# MCU.net
KiCad netlist of a schematic drawn in Altium Designer
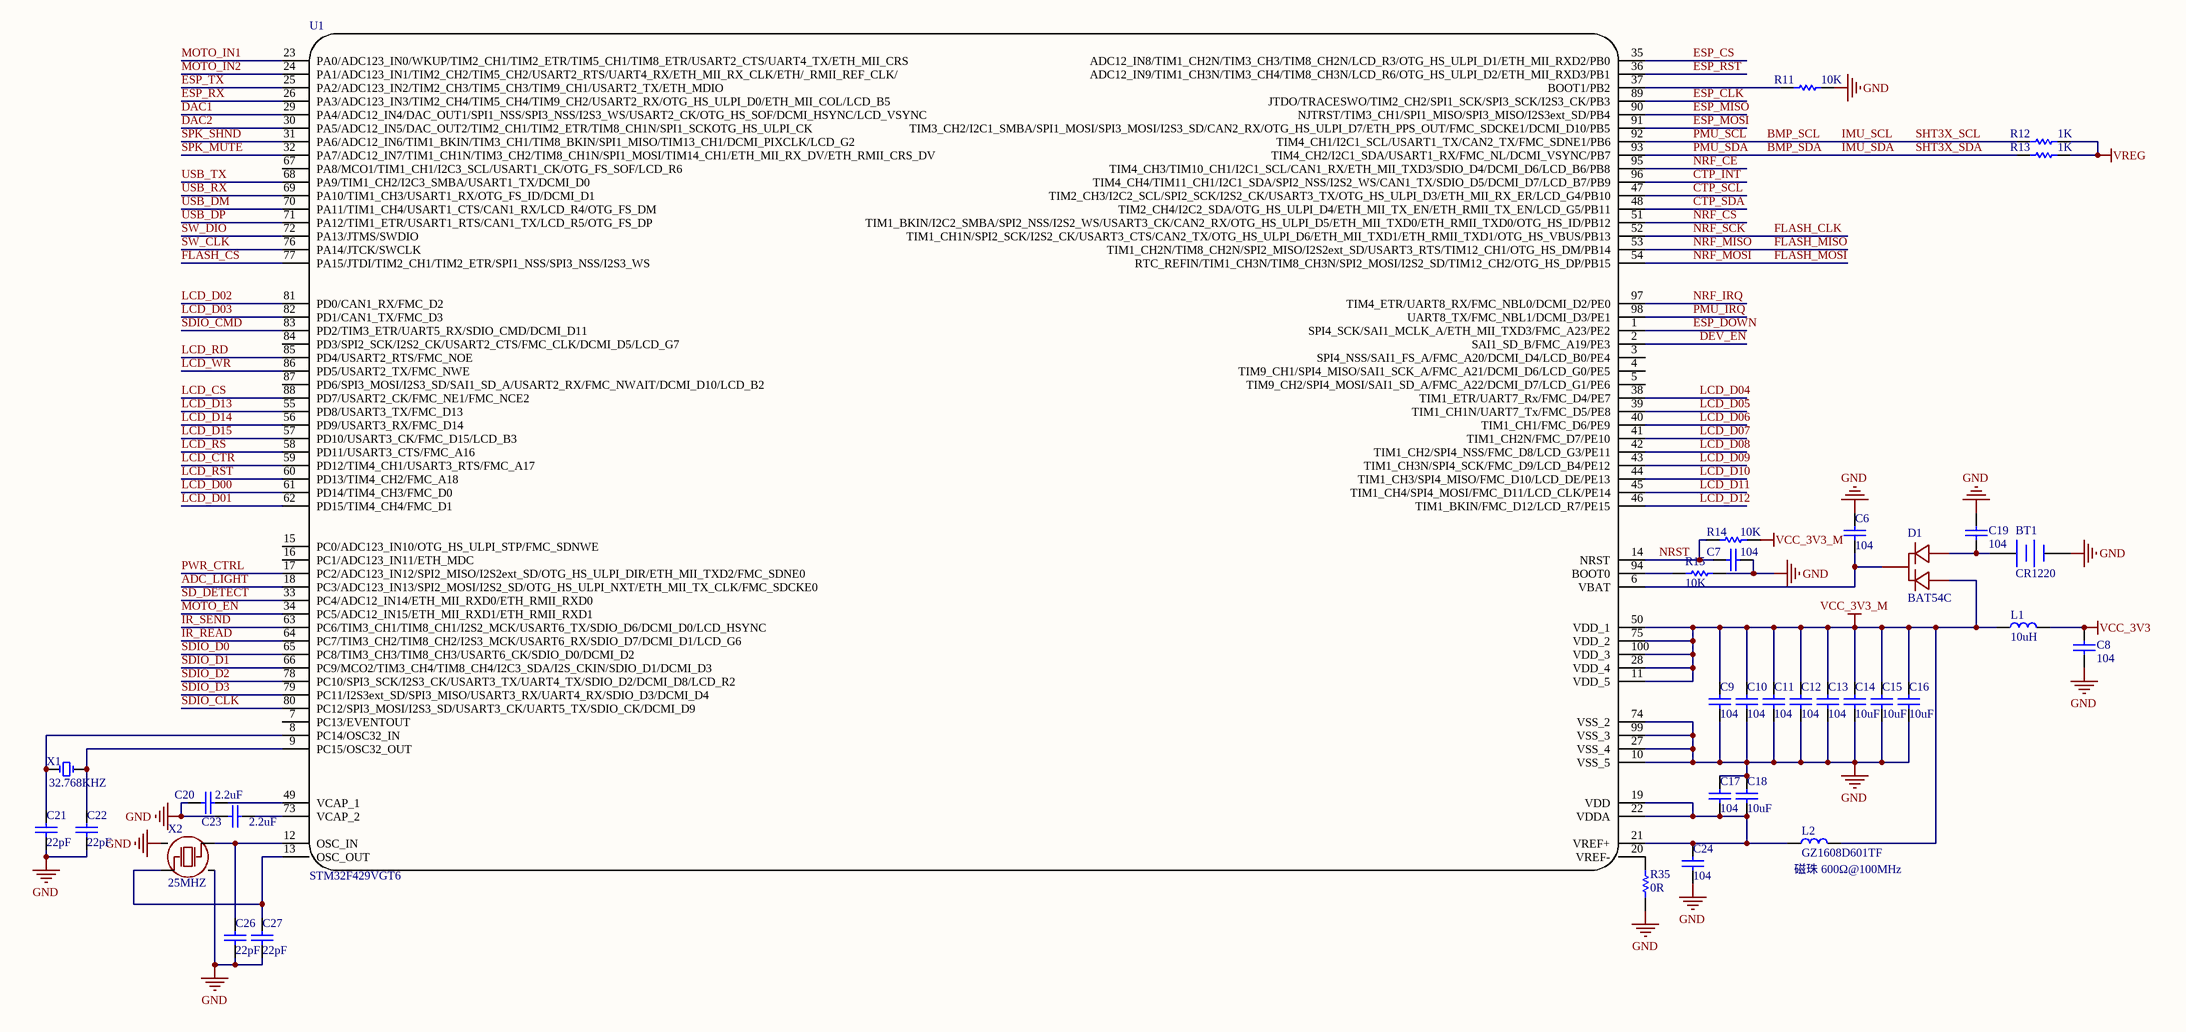
[diagram p0: MCU.SchDoc]

(export (version "E")
  (design (tool "Eeschema 10.0.6"))
  (components
    (comp (ref "BT1")
      (value "CR1220")
      (footprint "CR1220-2")
      (description "Multicell Battery")
      (fields (field (name "PUBLISHER") "Altium Limited"))
      (libsource (lib "Miscellaneous Devices") (part "Battery"))
    )
    (comp (ref "C6") (value "104") (footprint "C 0603") (libsource (lib "Sheet") (part "CAP")))
    (comp (ref "C7") (value "104") (footprint "C 0603") (libsource (lib "Sheet") (part "CAP")))
    (comp (ref "C8") (value "104") (footprint "C 0603") (libsource (lib "Sheet") (part "CAP")))
    (comp (ref "C9") (value "104") (footprint "C 0603") (libsource (lib "Sheet") (part "CAP")))
    (comp (ref "C10") (value "104") (footprint "C 0603") (libsource (lib "Sheet") (part "CAP")))
    (comp (ref "C11") (value "104") (footprint "C 0603") (libsource (lib "Sheet") (part "CAP")))
    (comp (ref "C12") (value "104") (footprint "C 0603") (libsource (lib "Sheet") (part "CAP")))
    (comp (ref "C13") (value "104") (footprint "C 0603") (libsource (lib "Sheet") (part "CAP")))
    (comp (ref "C14") (value "10uF") (footprint "C 0603") (libsource (lib "Sheet") (part "CAP")))
    (comp (ref "C15") (value "10uF") (footprint "C 0603") (libsource (lib "Sheet") (part "CAP")))
    (comp (ref "C16") (value "10uF") (footprint "C 0603") (libsource (lib "Sheet") (part "CAP")))
    (comp (ref "C17") (value "104") (footprint "C 0603") (libsource (lib "Sheet") (part "CAP")))
    (comp (ref "C18") (value "10uF") (footprint "C 0603") (libsource (lib "Sheet") (part "CAP")))
    (comp (ref "C19") (value "104") (footprint "C 0603") (libsource (lib "Sheet") (part "CAP")))
    (comp (ref "C20") (value "2.2uF") (footprint "C 0603") (libsource (lib "Sheet") (part "CAP")))
    (comp (ref "C21") (value "22pF") (footprint "C 0603") (libsource (lib "Sheet") (part "CAP")))
    (comp (ref "C22") (value "22pF") (footprint "C 0603") (libsource (lib "Sheet") (part "CAP")))
    (comp (ref "C23") (value "2.2uF") (footprint "C 0603") (libsource (lib "Sheet") (part "CAP")))
    (comp (ref "C24") (value "104") (footprint "C 0603") (libsource (lib "Sheet") (part "CAP")))
    (comp (ref "C26") (value "22pF") (footprint "C 0603") (libsource (lib "Sheet") (part "CAP")))
    (comp (ref "C27") (value "22pF") (footprint "C 0603") (libsource (lib "Sheet") (part "CAP")))
    (comp (ref "D1") (value "BAT54C") (footprint "SOT-23") (libsource (lib "Sheet") (part "BAT54C")))
    (comp (ref "L1") (value "10uH") (footprint "L 0603") (libsource (lib "Sheet") (part "INDUCTOR")))
    (comp (ref "L2") (value "GZ1608D601TF") (footprint "L 0603") (libsource (lib "Sheet") (part "INDUCTOR")))
    (comp (ref "R11") (value "10K") (footprint "R 0603") (libsource (lib "Sheet") (part "RES")))
    (comp (ref "R12") (value "1K") (footprint "R 0603") (libsource (lib "Sheet") (part "RES")))
    (comp (ref "R13") (value "1K") (footprint "R 0603") (libsource (lib "Sheet") (part "RES")))
    (comp (ref "R14") (value "10K") (footprint "R 0603") (libsource (lib "Sheet") (part "RES")))
    (comp (ref "R15") (value "10K") (footprint "R 0603") (libsource (lib "Sheet") (part "RES")))
    (comp (ref "R35") (value "0R") (footprint "R 0603") (libsource (lib "Sheet") (part "RES")))
    (comp (ref "U1")
      (value "STM32F429VGT6")
      (footprint "LQFP100")
      (libsource (lib "Sheet") (part "STM32F429VGT6"))
    )
    (comp (ref "X1")
      (value "32.768KHZ")
      (footprint "XTAL-3215")
      (libsource (lib "Bison-Board") (part "XTAL-2P"))
    )
    (comp (ref "X2") (value "25MHZ") (footprint "SMD-3225") (libsource (lib "Sheet") (part "XTAL-4P")))
  )
  (nets
    (net (code "1") (name "/ADC_LIGHT") (class "Default")
      (node (ref "U1") (pin "18") (pinfunction "PC3/ADC123_IN13/SPI2_MOSI/I2S2_SD/OTG_HS_ULPI_NXT/ETH_MII_TX_CLK/FMC_SDCKE0_18") (pintype "passive"))
    )
    (net (code "2") (name "/BMP_SCL") (class "Default")
      (node (ref "R12") (pin "1") (pinfunction "1_1") (pintype "passive"))
      (node (ref "U1") (pin "92") (pinfunction "TIM4_CH1/I2C1_SCL/USART1_TX/CAN2_TX/FMC_SDNE1/PB6_92") (pintype "passive"))
    )
    (net (code "3") (name "/BMP_SDA") (class "Default")
      (node (ref "R13") (pin "1") (pinfunction "1_1") (pintype "passive"))
      (node (ref "U1") (pin "93") (pinfunction "TIM4_CH2/I2C1_SDA/USART1_RX/FMC_NL/DCMI_VSYNC/PB7_93") (pintype "passive"))
    )
    (net (code "4") (name "/CTP_INT") (class "Default")
      (node (ref "U1") (pin "96") (pinfunction "TIM4_CH4/TIM11_CH1/I2C1_SDA/SPI2_NSS/I2S2_WS/CAN1_TX/SDIO_D5/DCMI_D7/LCD_B7/PB9_96") (pintype "passive"))
    )
    (net (code "5") (name "/CTP_SCL") (class "Default")
      (node (ref "U1") (pin "47") (pinfunction "TIM2_CH3/I2C2_SCL/SPI2_SCK/I2S2_CK/USART3_TX/OTG_HS_ULPI_D3/ETH_MII_RX_ER/LCD_G4/PB10_47") (pintype "passive"))
    )
    (net (code "6") (name "/CTP_SDA") (class "Default")
      (node (ref "U1") (pin "48") (pinfunction "TIM2_CH4/I2C2_SDA/OTG_HS_ULPI_D4/ETH_MII_TX_EN/ETH_RMII_TX_EN/LCD_G5/PB11_48") (pintype "passive"))
    )
    (net (code "7") (name "/DAC1") (class "Default")
      (node (ref "U1") (pin "29") (pinfunction "PA4/ADC12_IN4/DAC_OUT1/SPI1_NSS/SPI3_NSS/I2S3_WS/USART2_CK/OTG_HS_SOF/DCMI_HSYNC/LCD_VSYNC_29") (pintype "passive"))
    )
    (net (code "8") (name "/DAC2") (class "Default")
      (node (ref "U1") (pin "30") (pinfunction "PA5/ADC12_IN5/DAC_OUT2/TIM2_CH1/TIM2_ETR/TIM8_CH1N/SPI1_SCKOTG_HS_ULPI_CK_30") (pintype "passive"))
    )
    (net (code "9") (name "/DEV_EN") (class "Default")
      (node (ref "U1") (pin "2") (pinfunction "SAI1_SD_B/FMC_A19/PE3_2") (pintype "passive"))
    )
    (net (code "10") (name "/ESP_CLK") (class "Default")
      (node (ref "U1") (pin "89") (pinfunction "JTDO/TRACESWO/TIM2_CH2/SPI1_SCK/SPI3_SCK/I2S3_CK/PB3_89") (pintype "passive"))
    )
    (net (code "11") (name "/ESP_CS") (class "Default")
      (node (ref "U1") (pin "35") (pinfunction "ADC12_IN8/TIM1_CH2N/TIM3_CH3/TIM8_CH2N/LCD_R3/OTG_HS_ULPI_D1/ETH_MII_RXD2/PB0_35") (pintype "passive"))
    )
    (net (code "12") (name "/ESP_DOWN") (class "Default")
      (node (ref "U1") (pin "1") (pinfunction "SPI4_SCK/SAI1_MCLK_A/ETH_MII_TXD3/FMC_A23/PE2_1") (pintype "passive"))
    )
    (net (code "13") (name "/ESP_MISO") (class "Default")
      (node (ref "U1") (pin "90") (pinfunction "NJTRST/TIM3_CH1/SPI1_MISO/SPI3_MISO/I2S3ext_SD/PB4_90") (pintype "passive"))
    )
    (net (code "14") (name "/ESP_MOSI") (class "Default")
      (node (ref "U1") (pin "91") (pinfunction "TIM3_CH2/I2C1_SMBA/SPI1_MOSI/SPI3_MOSI/I2S3_SD/CAN2_RX/OTG_HS_ULPI_D7/ETH_PPS_OUT/FMC_SDCKE1/DCMI_D10/PB5_91") (pintype "passive"))
    )
    (net (code "15") (name "/ESP_RST") (class "Default")
      (node (ref "U1") (pin "36") (pinfunction "ADC12_IN9/TIM1_CH3N/TIM3_CH4/TIM8_CH3N/LCD_R6/OTG_HS_ULPI_D2/ETH_MII_RXD3/PB1_36") (pintype "passive"))
    )
    (net (code "16") (name "/ESP_RX") (class "Default")
      (node (ref "U1") (pin "26") (pinfunction "PA3/ADC123_IN3/TIM2_CH4/TIM5_CH4/TIM9_CH2/USART2_RX/OTG_HS_ULPI_D0/ETH_MII_COL/LCD_B5_26") (pintype "passive"))
    )
    (net (code "17") (name "/ESP_TX") (class "Default")
      (node (ref "U1") (pin "25") (pinfunction "PA2/ADC123_IN2/TIM2_CH3/TIM5_CH3/TIM9_CH1/USART2_TX/ETH_MDIO_25") (pintype "passive"))
    )
    (net (code "18") (name "/FLASH_CLK") (class "Default")
      (node (ref "U1") (pin "52") (pinfunction "TIM1_CH1N/SPI2_SCK/I2S2_CK/USART3_CTS/CAN2_TX/OTG_HS_ULPI_D6/ETH_MII_TXD1/ETH_RMII_TXD1/OTG_HS_VBUS/PB13_52") (pintype "passive"))
    )
    (net (code "19") (name "/FLASH_CS") (class "Default")
      (node (ref "U1") (pin "77") (pinfunction "PA15/JTDI/TIM2_CH1/TIM2_ETR/SPI1_NSS/SPI3_NSS/I2S3_WS_77") (pintype "passive"))
    )
    (net (code "20") (name "/FLASH_MISO") (class "Default")
      (node (ref "U1") (pin "53") (pinfunction "TIM1_CH2N/TIM8_CH2N/SPI2_MISO/I2S2ext_SD/USART3_RTS/TIM12_CH1/OTG_HS_DM/PB14_53") (pintype "passive"))
    )
    (net (code "21") (name "/FLASH_MOSI") (class "Default")
      (node (ref "U1") (pin "54") (pinfunction "RTC_REFIN/TIM1_CH3N/TIM8_CH3N/SPI2_MOSI/I2S2_SD/TIM12_CH2/OTG_HS_DP/PB15_54") (pintype "passive"))
    )
    (net (code "22") (name "/IR_READ") (class "Default")
      (node (ref "U1") (pin "64") (pinfunction "PC7/TIM3_CH2/TIM8_CH2/I2S3_MCK/USART6_RX/SDIO_D7/DCMI_D1/LCD_G6_64") (pintype "passive"))
    )
    (net (code "23") (name "/IR_SEND") (class "Default")
      (node (ref "U1") (pin "63") (pinfunction "PC6/TIM3_CH1/TIM8_CH1/I2S2_MCK/USART6_TX/SDIO_D6/DCMI_D0/LCD_HSYNC_63") (pintype "passive"))
    )
    (net (code "24") (name "/LCD_CS") (class "Default")
      (node (ref "U1") (pin "88") (pinfunction "PD7/USART2_CK/FMC_NE1/FMC_NCE2_88") (pintype "passive"))
    )
    (net (code "25") (name "/LCD_CTR") (class "Default")
      (node (ref "U1") (pin "59") (pinfunction "PD12/TIM4_CH1/USART3_RTS/FMC_A17_59") (pintype "passive"))
    )
    (net (code "26") (name "/LCD_D00") (class "Default")
      (node (ref "U1") (pin "61") (pinfunction "PD14/TIM4_CH3/FMC_D0_61") (pintype "passive"))
    )
    (net (code "27") (name "/LCD_D01") (class "Default")
      (node (ref "U1") (pin "62") (pinfunction "PD15/TIM4_CH4/FMC_D1_62") (pintype "passive"))
    )
    (net (code "28") (name "/LCD_D02") (class "Default")
      (node (ref "U1") (pin "81") (pinfunction "PD0/CAN1_RX/FMC_D2_81") (pintype "passive"))
    )
    (net (code "29") (name "/LCD_D03") (class "Default")
      (node (ref "U1") (pin "82") (pinfunction "PD1/CAN1_TX/FMC_D3_82") (pintype "passive"))
    )
    (net (code "30") (name "/LCD_D04") (class "Default")
      (node (ref "U1") (pin "38") (pinfunction "TIM1_ETR/UART7_Rx/FMC_D4/PE7_38") (pintype "passive"))
    )
    (net (code "31") (name "/LCD_D05") (class "Default")
      (node (ref "U1") (pin "39") (pinfunction "TIM1_CH1N/UART7_Tx/FMC_D5/PE8_39") (pintype "passive"))
    )
    (net (code "32") (name "/LCD_D06") (class "Default")
      (node (ref "U1") (pin "40") (pinfunction "TIM1_CH1/FMC_D6/PE9_40") (pintype "passive"))
    )
    (net (code "33") (name "/LCD_D07") (class "Default")
      (node (ref "U1") (pin "41") (pinfunction "TIM1_CH2N/FMC_D7/PE10_41") (pintype "passive"))
    )
    (net (code "34") (name "/LCD_D08") (class "Default")
      (node (ref "U1") (pin "42") (pinfunction "TIM1_CH2/SPI4_NSS/FMC_D8/LCD_G3/PE11_42") (pintype "passive"))
    )
    (net (code "35") (name "/LCD_D09") (class "Default")
      (node (ref "U1") (pin "43") (pinfunction "TIM1_CH3N/SPI4_SCK/FMC_D9/LCD_B4/PE12_43") (pintype "passive"))
    )
    (net (code "36") (name "/LCD_D10") (class "Default")
      (node (ref "U1") (pin "44") (pinfunction "TIM1_CH3/SPI4_MISO/FMC_D10/LCD_DE/PE13_44") (pintype "passive"))
    )
    (net (code "37") (name "/LCD_D11") (class "Default")
      (node (ref "U1") (pin "45") (pinfunction "TIM1_CH4/SPI4_MOSI/FMC_D11/LCD_CLK/PE14_45") (pintype "passive"))
    )
    (net (code "38") (name "/LCD_D12") (class "Default")
      (node (ref "U1") (pin "46") (pinfunction "TIM1_BKIN/FMC_D12/LCD_R7/PE15_46") (pintype "passive"))
    )
    (net (code "39") (name "/LCD_D13") (class "Default")
      (node (ref "U1") (pin "55") (pinfunction "PD8/USART3_TX/FMC_D13_55") (pintype "passive"))
    )
    (net (code "40") (name "/LCD_D14") (class "Default")
      (node (ref "U1") (pin "56") (pinfunction "PD9/USART3_RX/FMC_D14_56") (pintype "passive"))
    )
    (net (code "41") (name "/LCD_D15") (class "Default")
      (node (ref "U1") (pin "57") (pinfunction "PD10/USART3_CK/FMC_D15/LCD_B3_57") (pintype "passive"))
    )
    (net (code "42") (name "/LCD_RD") (class "Default")
      (node (ref "U1") (pin "85") (pinfunction "PD4/USART2_RTS/FMC_NOE_85") (pintype "passive"))
    )
    (net (code "43") (name "/LCD_RS") (class "Default")
      (node (ref "U1") (pin "58") (pinfunction "PD11/USART3_CTS/FMC_A16_58") (pintype "passive"))
    )
    (net (code "44") (name "/LCD_RST") (class "Default")
      (node (ref "U1") (pin "60") (pinfunction "PD13/TIM4_CH2/FMC_A18_60") (pintype "passive"))
    )
    (net (code "45") (name "/LCD_WR") (class "Default")
      (node (ref "U1") (pin "86") (pinfunction "PD5/USART2_TX/FMC_NWE_86") (pintype "passive"))
    )
    (net (code "46") (name "/MOTO_EN") (class "Default")
      (node (ref "U1") (pin "34") (pinfunction "PC5/ADC12_IN15/ETH_MII_RXD1/ETH_RMII_RXD1_34") (pintype "passive"))
    )
    (net (code "47") (name "/MOTO_IN1") (class "Default")
      (node (ref "U1") (pin "23") (pinfunction "PA0/ADC123_IN0/WKUP/TIM2_CH1/TIM2_ETR/TIM5_CH1/TIM8_ETR/USART2_CTS/UART4_TX/ETH_MII_CRS_23") (pintype "passive"))
    )
    (net (code "48") (name "/MOTO_IN2") (class "Default")
      (node (ref "U1") (pin "24") (pinfunction "PA1/ADC123_IN1/TIM2_CH2/TIM5_CH2/USART2_RTS/UART4_RX/ETH_MII_RX_CLK/ETH/_RMII_REF_CLK/_24") (pintype "passive"))
    )
    (net (code "49") (name "/NRF_CE") (class "Default")
      (node (ref "U1") (pin "95") (pinfunction "TIM4_CH3/TIM10_CH1/I2C1_SCL/CAN1_RX/ETH_MII_TXD3/SDIO_D4/DCMI_D6/LCD_B6/PB8_95") (pintype "passive"))
    )
    (net (code "50") (name "/NRF_CS") (class "Default")
      (node (ref "U1") (pin "51") (pinfunction "TIM1_BKIN/I2C2_SMBA/SPI2_NSS/I2S2_WS/USART3_CK/CAN2_RX/OTG_HS_ULPI_D5/ETH_MII_TXD0/ETH_RMII_TXD0/OTG_HS_ID/PB12_51") (pintype "passive"))
    )
    (net (code "51") (name "/NRF_IRQ") (class "Default")
      (node (ref "U1") (pin "97") (pinfunction "TIM4_ETR/UART8_RX/FMC_NBL0/DCMI_D2/PE0_97") (pintype "passive"))
    )
    (net (code "52") (name "/NRST") (class "Default")
      (node (ref "C7") (pin "2") (pinfunction "2_2") (pintype "passive"))
      (node (ref "R14") (pin "2") (pinfunction "2_2") (pintype "passive"))
      (node (ref "U1") (pin "14") (pinfunction "NRST_14") (pintype "passive"))
    )
    (net (code "53") (name "/PMU_IRQ") (class "Default")
      (node (ref "U1") (pin "98") (pinfunction "UART8_TX/FMC_NBL1/DCMI_D3/PE1_98") (pintype "passive"))
    )
    (net (code "54") (name "/PWR_CTRL") (class "Default")
      (node (ref "U1") (pin "17") (pinfunction "PC2/ADC123_IN12/SPI2_MISO/I2S2ext_SD/OTG_HS_ULPI_DIR/ETH_MII_TXD2/FMC_SDNE0_17") (pintype "passive"))
    )
    (net (code "55") (name "/SDIO_CLK") (class "Default")
      (node (ref "U1") (pin "80") (pinfunction "PC12/SPI3_MOSI/I2S3_SD/USART3_CK/UART5_TX/SDIO_CK/DCMI_D9_80") (pintype "passive"))
    )
    (net (code "56") (name "/SDIO_CMD") (class "Default")
      (node (ref "U1") (pin "83") (pinfunction "PD2/TIM3_ETR/UART5_RX/SDIO_CMD/DCMI_D11_83") (pintype "passive"))
    )
    (net (code "57") (name "/SDIO_D0") (class "Default")
      (node (ref "U1") (pin "65") (pinfunction "PC8/TIM3_CH3/TIM8_CH3/USART6_CK/SDIO_D0/DCMI_D2_65") (pintype "passive"))
    )
    (net (code "58") (name "/SDIO_D1") (class "Default")
      (node (ref "U1") (pin "66") (pinfunction "PC9/MCO2/TIM3_CH4/TIM8_CH4/I2C3_SDA/I2S_CKIN/SDIO_D1/DCMI_D3_66") (pintype "passive"))
    )
    (net (code "59") (name "/SDIO_D2") (class "Default")
      (node (ref "U1") (pin "78") (pinfunction "PC10/SPI3_SCK/I2S3_CK/USART3_TX/UART4_TX/SDIO_D2/DCMI_D8/LCD_R2_78") (pintype "passive"))
    )
    (net (code "60") (name "/SDIO_D3") (class "Default")
      (node (ref "U1") (pin "79") (pinfunction "PC11/I2S3ext_SD/SPI3_MISO/USART3_RX/UART4_RX/SDIO_D3/DCMI_D4_79") (pintype "passive"))
    )
    (net (code "61") (name "/SD_DETECT") (class "Default")
      (node (ref "U1") (pin "33") (pinfunction "PC4/ADC12_IN14/ETH_MII_RXD0/ETH_RMII_RXD0_33") (pintype "passive"))
    )
    (net (code "62") (name "/SPK_MUTE") (class "Default")
      (node (ref "U1") (pin "32") (pinfunction "PA7/ADC12_IN7/TIM1_CH1N/TIM3_CH2/TIM8_CH1N/SPI1_MOSI/TIM14_CH1/ETH_MII_RX_DV/ETH_RMII_CRS_DV_32") (pintype "passive"))
    )
    (net (code "63") (name "/SPK_SHND") (class "Default")
      (node (ref "U1") (pin "31") (pinfunction "PA6/ADC12_IN6/TIM1_BKIN/TIM3_CH1/TIM8_BKIN/SPI1_MISO/TIM13_CH1/DCMI_PIXCLK/LCD_G2_31") (pintype "passive"))
    )
    (net (code "64") (name "/SW_CLK") (class "Default")
      (node (ref "U1") (pin "76") (pinfunction "PA14/JTCK/SWCLK_76") (pintype "passive"))
    )
    (net (code "65") (name "/SW_DIO") (class "Default")
      (node (ref "U1") (pin "72") (pinfunction "PA13/JTMS/SWDIO_72") (pintype "passive"))
    )
    (net (code "66") (name "/USB_DM") (class "Default")
      (node (ref "U1") (pin "70") (pinfunction "PA11/TIM1_CH4/USART1_CTS/CAN1_RX/LCD_R4/OTG_FS_DM_70") (pintype "passive"))
    )
    (net (code "67") (name "/USB_DP") (class "Default")
      (node (ref "U1") (pin "71") (pinfunction "PA12/TIM1_ETR/USART1_RTS/CAN1_TX/LCD_R5/OTG_FS_DP_71") (pintype "passive"))
    )
    (net (code "68") (name "/USB_RX") (class "Default")
      (node (ref "U1") (pin "69") (pinfunction "PA10/TIM1_CH3/USART1_RX/OTG_FS_ID/DCMI_D1_69") (pintype "passive"))
    )
    (net (code "69") (name "/USB_TX") (class "Default")
      (node (ref "U1") (pin "68") (pinfunction "PA9/TIM1_CH2/I2C3_SMBA/USART1_TX/DCMI_D0_68") (pintype "passive"))
    )
    (net (code "70") (name "GND") (class "Default")
      (node (ref "BT1") (pin "2") (pinfunction "-_2") (pintype "passive"))
      (node (ref "C10") (pin "1") (pinfunction "1_1") (pintype "passive"))
      (node (ref "C11") (pin "1") (pinfunction "1_1") (pintype "passive"))
      (node (ref "C12") (pin "1") (pinfunction "1_1") (pintype "passive"))
      (node (ref "C13") (pin "1") (pinfunction "1_1") (pintype "passive"))
      (node (ref "C14") (pin "1") (pinfunction "1_1") (pintype "passive"))
      (node (ref "C15") (pin "1") (pinfunction "1_1") (pintype "passive"))
      (node (ref "C16") (pin "1") (pinfunction "1_1") (pintype "passive"))
      (node (ref "C17") (pin "2") (pinfunction "2_2") (pintype "passive"))
      (node (ref "C18") (pin "2") (pinfunction "2_2") (pintype "passive"))
      (node (ref "C19") (pin "1") (pinfunction "1_1") (pintype "passive"))
      (node (ref "C20") (pin "1") (pinfunction "1_1") (pintype "passive"))
      (node (ref "C21") (pin "1") (pinfunction "1_1") (pintype "passive"))
      (node (ref "C22") (pin "1") (pinfunction "1_1") (pintype "passive"))
      (node (ref "C23") (pin "1") (pinfunction "1_1") (pintype "passive"))
      (node (ref "C24") (pin "1") (pinfunction "1_1") (pintype "passive"))
      (node (ref "C26") (pin "1") (pinfunction "1_1") (pintype "passive"))
      (node (ref "C27") (pin "1") (pinfunction "1_1") (pintype "passive"))
      (node (ref "C6") (pin "2") (pinfunction "2_2") (pintype "passive"))
      (node (ref "C7") (pin "1") (pinfunction "1_1") (pintype "passive"))
      (node (ref "C8") (pin "1") (pinfunction "1_1") (pintype "passive"))
      (node (ref "C9") (pin "1") (pinfunction "1_1") (pintype "passive"))
      (node (ref "R11") (pin "2") (pinfunction "2_2") (pintype "passive"))
      (node (ref "R15") (pin "2") (pinfunction "2_2") (pintype "passive"))
      (node (ref "R35") (pin "1") (pinfunction "1_1") (pintype "passive"))
      (node (ref "U1") (pin "10") (pinfunction "VSS_5_10") (pintype "passive"))
      (node (ref "U1") (pin "27") (pinfunction "VSS_4_27") (pintype "passive"))
      (node (ref "U1") (pin "74") (pinfunction "VSS_2_74") (pintype "passive"))
      (node (ref "U1") (pin "99") (pinfunction "VSS_3_99") (pintype "passive"))
      (node (ref "X2") (pin "2") (pinfunction "2_2") (pintype "passive"))
      (node (ref "X2") (pin "4") (pinfunction "4_4") (pintype "passive"))
    )
    (net (code "71") (name "Net-(BT1-+)") (class "Default")
      (node (ref "BT1") (pin "1") (pinfunction "+_1") (pintype "passive"))
      (node (ref "C19") (pin "2") (pinfunction "2_2") (pintype "passive"))
      (node (ref "D1") (pin "2") (pinfunction "A_2") (pintype "passive"))
    )
    (net (code "72") (name "Net-(D1-C)") (class "Default")
      (node (ref "C6") (pin "1") (pinfunction "1_1") (pintype "passive"))
      (node (ref "D1") (pin "3") (pinfunction "C_3") (pintype "passive"))
      (node (ref "U1") (pin "6") (pinfunction "VBAT_6") (pintype "passive"))
    )
    (net (code "73") (name "Net-(U1-BOOT0)") (class "Default")
      (node (ref "R15") (pin "1") (pinfunction "1_1") (pintype "passive"))
      (node (ref "U1") (pin "94") (pinfunction "BOOT0_94") (pintype "passive"))
    )
    (net (code "74") (name "Net-(U1-BOOT1{slash}PB2)") (class "Default")
      (node (ref "R11") (pin "1") (pinfunction "1_1") (pintype "passive"))
      (node (ref "U1") (pin "37") (pinfunction "BOOT1/PB2_37") (pintype "passive"))
    )
    (net (code "75") (name "Net-(U1-OSC_IN)") (class "Default")
      (node (ref "C26") (pin "2") (pinfunction "2_2") (pintype "passive"))
      (node (ref "U1") (pin "12") (pinfunction "OSC_IN_12") (pintype "passive"))
      (node (ref "X2") (pin "3") (pinfunction "3_3") (pintype "passive"))
    )
    (net (code "76") (name "Net-(U1-OSC_OUT)") (class "Default")
      (node (ref "C27") (pin "2") (pinfunction "2_2") (pintype "passive"))
      (node (ref "U1") (pin "13") (pinfunction "OSC_OUT_13") (pintype "passive"))
      (node (ref "X2") (pin "1") (pinfunction "1_1") (pintype "passive"))
    )
    (net (code "77") (name "Net-(U1-PC14{slash}OSC32_IN)") (class "Default")
      (node (ref "C21") (pin "2") (pinfunction "2_2") (pintype "passive"))
      (node (ref "U1") (pin "8") (pinfunction "PC14/OSC32_IN_8") (pintype "passive"))
      (node (ref "X1") (pin "1") (pinfunction "1_1") (pintype "passive"))
    )
    (net (code "78") (name "Net-(U1-PC15{slash}OSC32_OUT)") (class "Default")
      (node (ref "C22") (pin "2") (pinfunction "2_2") (pintype "passive"))
      (node (ref "U1") (pin "9") (pinfunction "PC15/OSC32_OUT_9") (pintype "passive"))
      (node (ref "X1") (pin "2") (pinfunction "2_2") (pintype "passive"))
    )
    (net (code "79") (name "Net-(U1-VCAP_1)") (class "Default")
      (node (ref "C20") (pin "2") (pinfunction "2_2") (pintype "passive"))
      (node (ref "U1") (pin "49") (pinfunction "VCAP_1_49") (pintype "passive"))
    )
    (net (code "80") (name "Net-(U1-VCAP_2)") (class "Default")
      (node (ref "C23") (pin "2") (pinfunction "2_2") (pintype "passive"))
      (node (ref "U1") (pin "73") (pinfunction "VCAP_2_73") (pintype "passive"))
    )
    (net (code "81") (name "Net-(U1-VDD)") (class "Default")
      (node (ref "C17") (pin "1") (pinfunction "1_1") (pintype "passive"))
      (node (ref "C18") (pin "1") (pinfunction "1_1") (pintype "passive"))
      (node (ref "C24") (pin "2") (pinfunction "2_2") (pintype "passive"))
      (node (ref "L2") (pin "1") (pinfunction "1_1") (pintype "passive"))
      (node (ref "U1") (pin "19") (pinfunction "VDD_19") (pintype "passive"))
      (node (ref "U1") (pin "21") (pinfunction "VREF+_21") (pintype "passive"))
      (node (ref "U1") (pin "22") (pinfunction "VDDA_22") (pintype "passive"))
    )
    (net (code "82") (name "Net-(U1-VREF-)") (class "Default")
      (node (ref "R35") (pin "2") (pinfunction "2_2") (pintype "passive"))
      (node (ref "U1") (pin "20") (pinfunction "VREF-_20") (pintype "passive"))
    )
    (net (code "83") (name "VCC_3V3") (class "Default")
      (node (ref "C8") (pin "2") (pinfunction "2_2") (pintype "passive"))
      (node (ref "L1") (pin "2") (pinfunction "2_2") (pintype "passive"))
    )
    (net (code "84") (name "VCC_3V3_M") (class "Default")
      (node (ref "C10") (pin "2") (pinfunction "2_2") (pintype "passive"))
      (node (ref "C11") (pin "2") (pinfunction "2_2") (pintype "passive"))
      (node (ref "C12") (pin "2") (pinfunction "2_2") (pintype "passive"))
      (node (ref "C13") (pin "2") (pinfunction "2_2") (pintype "passive"))
      (node (ref "C14") (pin "2") (pinfunction "2_2") (pintype "passive"))
      (node (ref "C15") (pin "2") (pinfunction "2_2") (pintype "passive"))
      (node (ref "C16") (pin "2") (pinfunction "2_2") (pintype "passive"))
      (node (ref "C9") (pin "2") (pinfunction "2_2") (pintype "passive"))
      (node (ref "D1") (pin "1") (pinfunction "A_1") (pintype "passive"))
      (node (ref "L1") (pin "1") (pinfunction "1_1") (pintype "passive"))
      (node (ref "L2") (pin "2") (pinfunction "2_2") (pintype "passive"))
      (node (ref "R14") (pin "1") (pinfunction "1_1") (pintype "passive"))
      (node (ref "U1") (pin "100") (pinfunction "VDD_3_100") (pintype "passive"))
      (node (ref "U1") (pin "11") (pinfunction "VDD_5_11") (pintype "passive"))
      (node (ref "U1") (pin "28") (pinfunction "VDD_4_28") (pintype "passive"))
      (node (ref "U1") (pin "50") (pinfunction "VDD_1_50") (pintype "passive"))
      (node (ref "U1") (pin "75") (pinfunction "VDD_2_75") (pintype "passive"))
    )
    (net (code "85") (name "VREG") (class "Default")
      (node (ref "R12") (pin "2") (pinfunction "2_2") (pintype "passive"))
      (node (ref "R13") (pin "2") (pinfunction "2_2") (pintype "passive"))
    )
    (net (code "86") (name "unconnected-(U1-PA8{slash}MCO1{slash}TIM1_CH1{slash}I2C3_SCL{slash}USART1_CK{slash}OTG_FS_SOF{slash}LCD_R6-Pad67)") (class "Default")
      (node (ref "U1") (pin "67") (pinfunction "PA8/MCO1/TIM1_CH1/I2C3_SCL/USART1_CK/OTG_FS_SOF/LCD_R6_67") (pintype "passive"))
    )
    (net (code "87") (name "unconnected-(U1-PC0{slash}ADC123_IN10{slash}OTG_HS_ULPI_STP{slash}FMC_SDNWE-Pad15)") (class "Default")
      (node (ref "U1") (pin "15") (pinfunction "PC0/ADC123_IN10/OTG_HS_ULPI_STP/FMC_SDNWE_15") (pintype "passive"))
    )
    (net (code "88") (name "unconnected-(U1-PC1{slash}ADC123_IN11{slash}ETH_MDC-Pad16)") (class "Default")
      (node (ref "U1") (pin "16") (pinfunction "PC1/ADC123_IN11/ETH_MDC_16") (pintype "passive"))
    )
    (net (code "89") (name "unconnected-(U1-PC13{slash}EVENTOUT-Pad7)") (class "Default")
      (node (ref "U1") (pin "7") (pinfunction "PC13/EVENTOUT_7") (pintype "passive"))
    )
    (net (code "90") (name "unconnected-(U1-PD3{slash}SPI2_SCK{slash}I2S2_CK{slash}USART2_CTS{slash}FMC_CLK{slash}DCMI_D5{slash}LCD_G7-Pad84)") (class "Default")
      (node (ref "U1") (pin "84") (pinfunction "PD3/SPI2_SCK/I2S2_CK/USART2_CTS/FMC_CLK/DCMI_D5/LCD_G7_84") (pintype "passive"))
    )
    (net (code "91") (name "unconnected-(U1-PD6{slash}SPI3_MOSI{slash}I2S3_SD{slash}SAI1_SD_A{slash}USART2_RX{slash}FMC_NWAIT{slash}DCMI_D10{slash}LCD_B2-Pad87)") (class "Default")
      (node (ref "U1") (pin "87") (pinfunction "PD6/SPI3_MOSI/I2S3_SD/SAI1_SD_A/USART2_RX/FMC_NWAIT/DCMI_D10/LCD_B2_87") (pintype "passive"))
    )
    (net (code "92") (name "unconnected-(U1-SPI4_NSS{slash}SAI1_FS_A{slash}FMC_A20{slash}DCMI_D4{slash}LCD_B0{slash}PE4-Pad3)") (class "Default")
      (node (ref "U1") (pin "3") (pinfunction "SPI4_NSS/SAI1_FS_A/FMC_A20/DCMI_D4/LCD_B0/PE4_3") (pintype "passive"))
    )
    (net (code "93") (name "unconnected-(U1-TIM9_CH1{slash}SPI4_MISO{slash}SAI1_SCK_A{slash}FMC_A21{slash}DCMI_D6{slash}LCD_G0{slash}PE5-Pad4)") (class "Default")
      (node (ref "U1") (pin "4") (pinfunction "TIM9_CH1/SPI4_MISO/SAI1_SCK_A/FMC_A21/DCMI_D6/LCD_G0/PE5_4") (pintype "passive"))
    )
    (net (code "94") (name "unconnected-(U1-TIM9_CH2{slash}SPI4_MOSI{slash}SAI1_SD_A{slash}FMC_A22{slash}DCMI_D7{slash}LCD_G1{slash}PE6-Pad5)") (class "Default")
      (node (ref "U1") (pin "5") (pinfunction "TIM9_CH2/SPI4_MOSI/SAI1_SD_A/FMC_A22/DCMI_D7/LCD_G1/PE6_5") (pintype "passive"))
    )
  )
)
